# PM12VPowerSupp.net
KiCad netlist of a schematic drawn in EAGLE
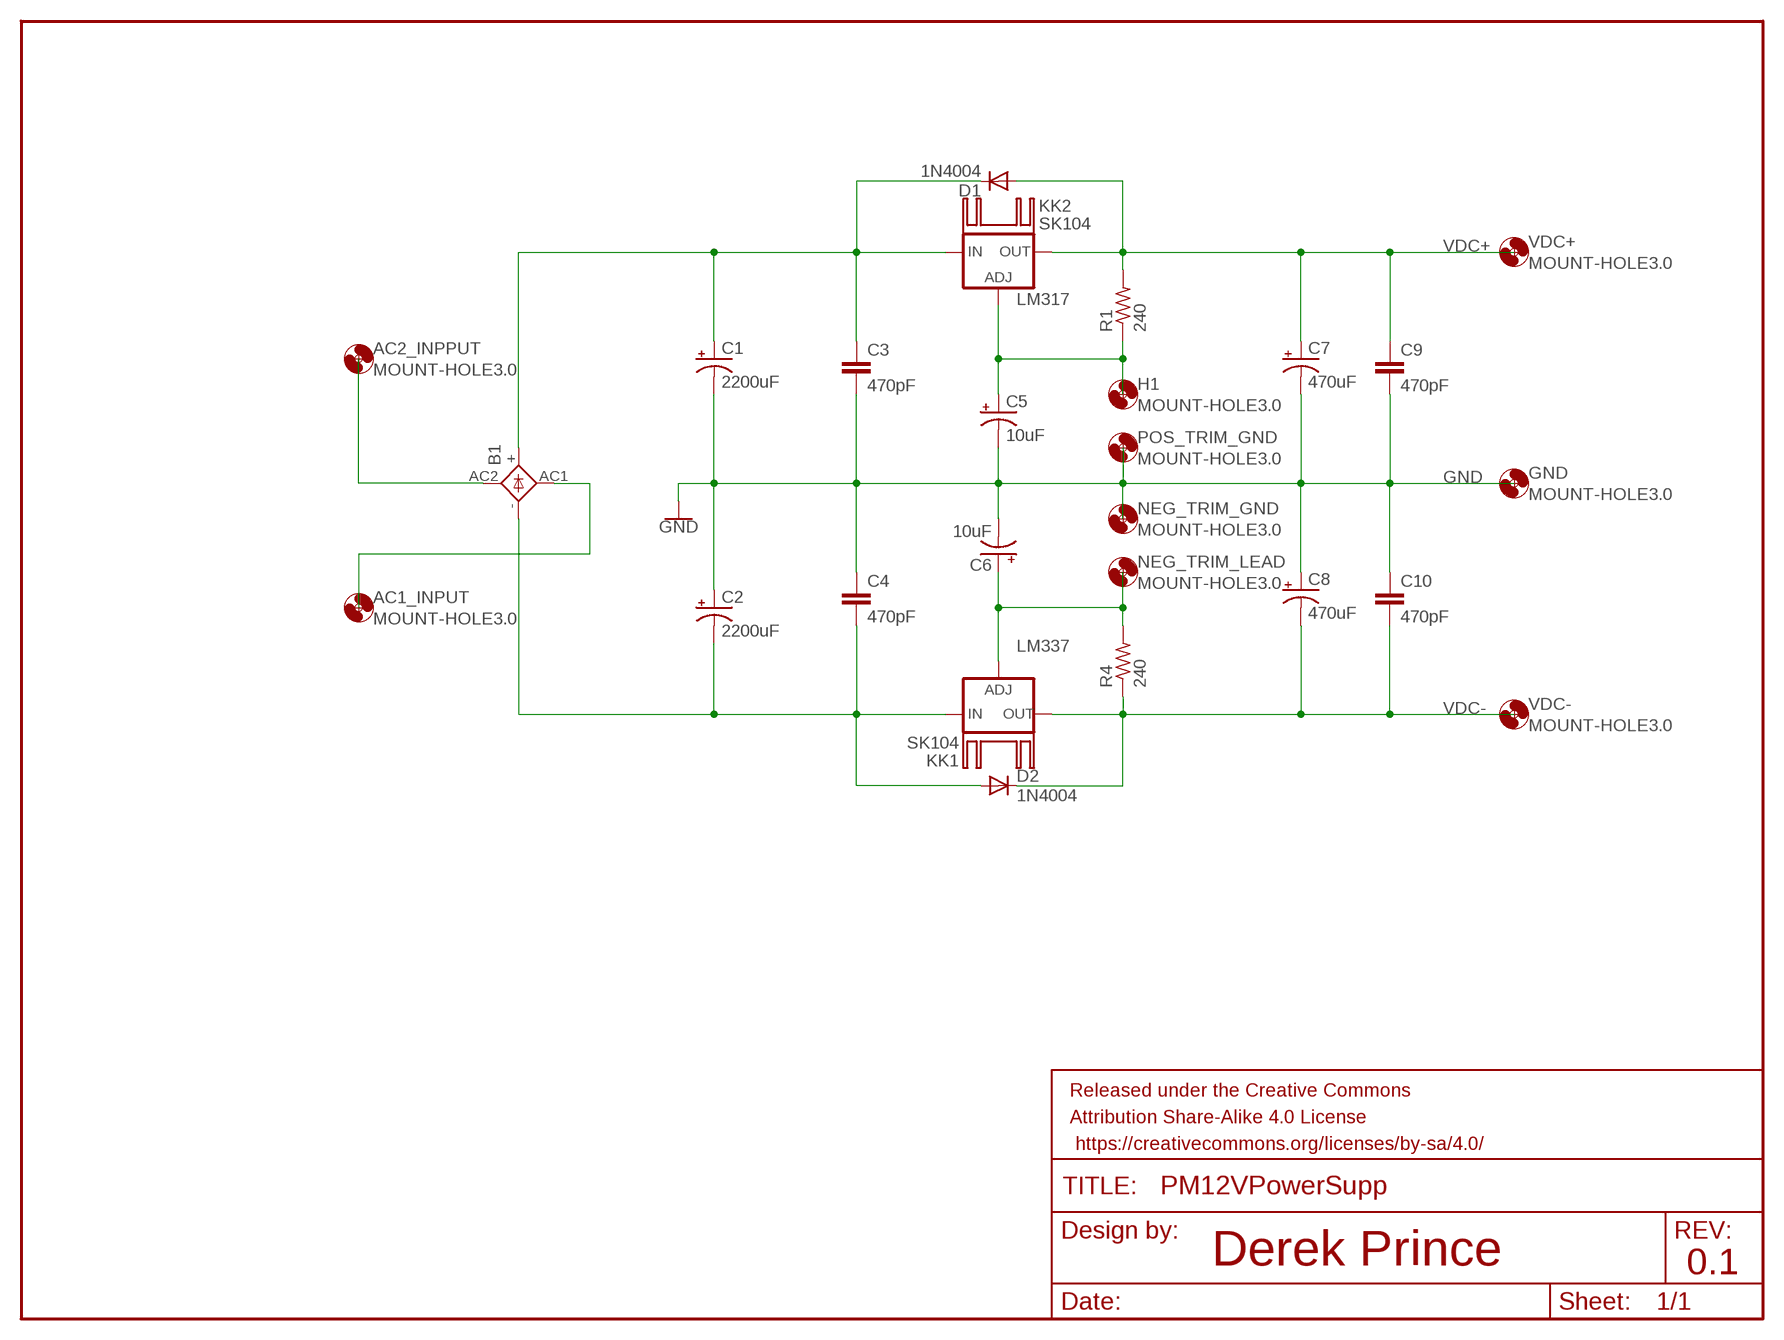
[diagram p0: schematic, sheet 1]

(export (version "E")
  (design (tool "Eeschema 10.0.6"))
  (components
    (comp (ref "AC1_INPUT")
      (value "MOUNT-HOLE3.0")
      (footprint "eagle-import:3,0")
      (libsource (lib "eagle-import") (part "MOUNT-HOLE3.0"))
    )
    (comp (ref "AC2_INPPUT")
      (value "MOUNT-HOLE3.0")
      (footprint "eagle-import:3,0")
      (libsource (lib "eagle-import") (part "MOUNT-HOLE3.0"))
    )
    (comp (ref "B1")
      (value "GBU4")
      (footprint "eagle-import:GBU4S")
      (libsource (lib "eagle-import") (part "GBU4"))
    )
    (comp (ref "C1")
      (value "2200uF")
      (footprint "eagle-import:E7,5-16")
      (libsource (lib "eagle-import") (part "CPOL-USE7.5-16"))
    )
    (comp (ref "C2")
      (value "2200uF")
      (footprint "eagle-import:E7,5-16")
      (libsource (lib "eagle-import") (part "CPOL-USE7.5-16"))
    )
    (comp (ref "C3")
      (value "470pF")
      (footprint "eagle-import:C050-024X044")
      (libsource (lib "eagle-import") (part "C-EU050-024X044"))
    )
    (comp (ref "C4")
      (value "470pF")
      (footprint "eagle-import:C050-024X044")
      (libsource (lib "eagle-import") (part "C-EU050-024X044"))
    )
    (comp (ref "C5")
      (value "10uF")
      (footprint "eagle-import:E2-5")
      (libsource (lib "eagle-import") (part "CPOL-USE2-5"))
    )
    (comp (ref "C6")
      (value "10uF")
      (footprint "eagle-import:E2-5")
      (libsource (lib "eagle-import") (part "CPOL-USE2-5"))
    )
    (comp (ref "C7")
      (value "470uF")
      (footprint "eagle-import:E5-10,5")
      (libsource (lib "eagle-import") (part "CPOL-USE5-10.5"))
    )
    (comp (ref "C8")
      (value "470uF")
      (footprint "eagle-import:E5-10,5")
      (libsource (lib "eagle-import") (part "CPOL-USE5-10.5"))
    )
    (comp (ref "C9")
      (value "470pF")
      (footprint "eagle-import:C050-024X044")
      (libsource (lib "eagle-import") (part "C-EU050-024X044"))
    )
    (comp (ref "C10")
      (value "470pF")
      (footprint "eagle-import:C050-024X044")
      (libsource (lib "eagle-import") (part "C-EU050-024X044"))
    )
    (comp (ref "D1")
      (value "1N4004")
      (footprint "eagle-import:DO41-10")
      (libsource (lib "eagle-import") (part "1N4004"))
    )
    (comp (ref "D2")
      (value "1N4004")
      (footprint "eagle-import:DO41-10")
      (libsource (lib "eagle-import") (part "1N4004"))
    )
    (comp (ref "FRAME1")
      (value "FRAME-LETTER")
      (footprint "eagle-import:CREATIVE_COMMONS")
      (libsource (lib "eagle-import") (part "FRAME-LETTER"))
    )
    (comp (ref "GND")
      (value "MOUNT-HOLE3.0")
      (footprint "eagle-import:3,0")
      (libsource (lib "eagle-import") (part "MOUNT-HOLE3.0"))
    )
    (comp (ref "H1")
      (value "MOUNT-HOLE3.0")
      (footprint "eagle-import:3,0")
      (libsource (lib "eagle-import") (part "MOUNT-HOLE3.0"))
    )
    (comp (ref "KK1")
      (value "SK104")
      (footprint "eagle-import:SK104")
      (libsource (lib "eagle-import") (part "SK104"))
    )
    (comp (ref "KK2")
      (value "SK104")
      (footprint "eagle-import:SK104")
      (libsource (lib "eagle-import") (part "SK104"))
    )
    (comp (ref "LM317")
      (value "LM317TS")
      (footprint "eagle-import:317TS")
      (libsource (lib "eagle-import") (part "LM317TS"))
    )
    (comp (ref "LM337")
      (value "LM337TS")
      (footprint "eagle-import:337TS")
      (libsource (lib "eagle-import") (part "LM337TS"))
    )
    (comp (ref "NEG_TRIM_GND")
      (value "MOUNT-HOLE3.0")
      (footprint "eagle-import:3,0")
      (libsource (lib "eagle-import") (part "MOUNT-HOLE3.0"))
    )
    (comp (ref "NEG_TRIM_LEAD")
      (value "MOUNT-HOLE3.0")
      (footprint "eagle-import:3,0")
      (libsource (lib "eagle-import") (part "MOUNT-HOLE3.0"))
    )
    (comp (ref "POS_TRIM_GND")
      (value "MOUNT-HOLE3.0")
      (footprint "eagle-import:3,0")
      (libsource (lib "eagle-import") (part "MOUNT-HOLE3.0"))
    )
    (comp (ref "R1")
      (value "240")
      (footprint "eagle-import:0309_12")
      (libsource (lib "eagle-import") (part "R-US_0309/12"))
    )
    (comp (ref "R4")
      (value "240")
      (footprint "eagle-import:0309_12")
      (libsource (lib "eagle-import") (part "R-US_0309/12"))
    )
    (comp (ref "VDC+")
      (value "MOUNT-HOLE3.0")
      (footprint "eagle-import:3,0")
      (libsource (lib "eagle-import") (part "MOUNT-HOLE3.0"))
    )
    (comp (ref "VDC-")
      (value "MOUNT-HOLE3.0")
      (footprint "eagle-import:3,0")
      (libsource (lib "eagle-import") (part "MOUNT-HOLE3.0"))
    )
  )
  (nets
    (net (code "1") (name "/VDC+") (class "Default")
      (node (ref "C7") (pin "+") (pinfunction "+_+") (pintype "passive"))
      (node (ref "C9") (pin "1") (pinfunction "1_1") (pintype "passive"))
      (node (ref "D1") (pin "A") (pinfunction "A_A") (pintype "passive"))
      (node (ref "LM317") (pin "2") (pinfunction "OUT_2") (pintype "passive"))
      (node (ref "R1") (pin "2") (pinfunction "2_2") (pintype "passive"))
    )
    (net (code "2") (name "/VDC-") (class "Default")
      (node (ref "C10") (pin "2") (pinfunction "2_2") (pintype "passive"))
      (node (ref "C8") (pin "-") (pinfunction "-_-") (pintype "passive"))
      (node (ref "D2") (pin "C") (pinfunction "C_C") (pintype "passive"))
      (node (ref "LM337") (pin "3") (pinfunction "OUT_3") (pintype "passive"))
      (node (ref "R4") (pin "1") (pinfunction "1_1") (pintype "passive"))
    )
    (net (code "3") (name "GND") (class "Default")
      (node (ref "C1") (pin "-") (pinfunction "-_-") (pintype "passive"))
      (node (ref "C10") (pin "1") (pinfunction "1_1") (pintype "passive"))
      (node (ref "C2") (pin "+") (pinfunction "+_+") (pintype "passive"))
      (node (ref "C3") (pin "2") (pinfunction "2_2") (pintype "passive"))
      (node (ref "C4") (pin "1") (pinfunction "1_1") (pintype "passive"))
      (node (ref "C5") (pin "-") (pinfunction "-_-") (pintype "passive"))
      (node (ref "C6") (pin "-") (pinfunction "-_-") (pintype "passive"))
      (node (ref "C7") (pin "-") (pinfunction "-_-") (pintype "passive"))
      (node (ref "C8") (pin "+") (pinfunction "+_+") (pintype "passive"))
      (node (ref "C9") (pin "2") (pinfunction "2_2") (pintype "passive"))
    )
    (net (code "4") (name "Net-(LM317-ADJ)") (class "Default")
      (node (ref "C5") (pin "+") (pinfunction "+_+") (pintype "passive"))
      (node (ref "LM317") (pin "1") (pinfunction "ADJ_1") (pintype "input"))
      (node (ref "R1") (pin "1") (pinfunction "1_1") (pintype "passive"))
    )
    (net (code "5") (name "Net-(LM317-IN)") (class "Default")
      (node (ref "B1") (pin "+") (pinfunction "+_+") (pintype "passive"))
      (node (ref "C1") (pin "+") (pinfunction "+_+") (pintype "passive"))
      (node (ref "C3") (pin "1") (pinfunction "1_1") (pintype "passive"))
      (node (ref "D1") (pin "C") (pinfunction "C_C") (pintype "passive"))
      (node (ref "LM317") (pin "3") (pinfunction "IN_3") (pintype "input"))
    )
    (net (code "6") (name "Net-(LM337-ADJ)") (class "Default")
      (node (ref "C6") (pin "+") (pinfunction "+_+") (pintype "passive"))
      (node (ref "LM337") (pin "1") (pinfunction "ADJ_1") (pintype "input"))
      (node (ref "R4") (pin "2") (pinfunction "2_2") (pintype "passive"))
    )
    (net (code "7") (name "Net-(LM337-IN)") (class "Default")
      (node (ref "B1") (pin "-") (pinfunction "-_-") (pintype "passive"))
      (node (ref "C2") (pin "-") (pinfunction "-_-") (pintype "passive"))
      (node (ref "C4") (pin "2") (pinfunction "2_2") (pintype "passive"))
      (node (ref "D2") (pin "A") (pinfunction "A_A") (pintype "passive"))
      (node (ref "LM337") (pin "2") (pinfunction "IN_2") (pintype "input"))
    )
    (net (code "8") (name "unconnected-(B1-AC1-PadAC2)") (class "Default")
      (node (ref "B1") (pin "AC2") (pinfunction "AC1_AC2") (pintype "passive"))
    )
    (net (code "9") (name "unconnected-(B1-AC2-PadAC1)") (class "Default")
      (node (ref "B1") (pin "AC1") (pinfunction "AC2_AC1") (pintype "passive"))
    )
  )
)
